# SCH_Easy-eda-E-xmas-board_2024-12-05.net
KiCad netlist of a schematic drawn in EasyEDA
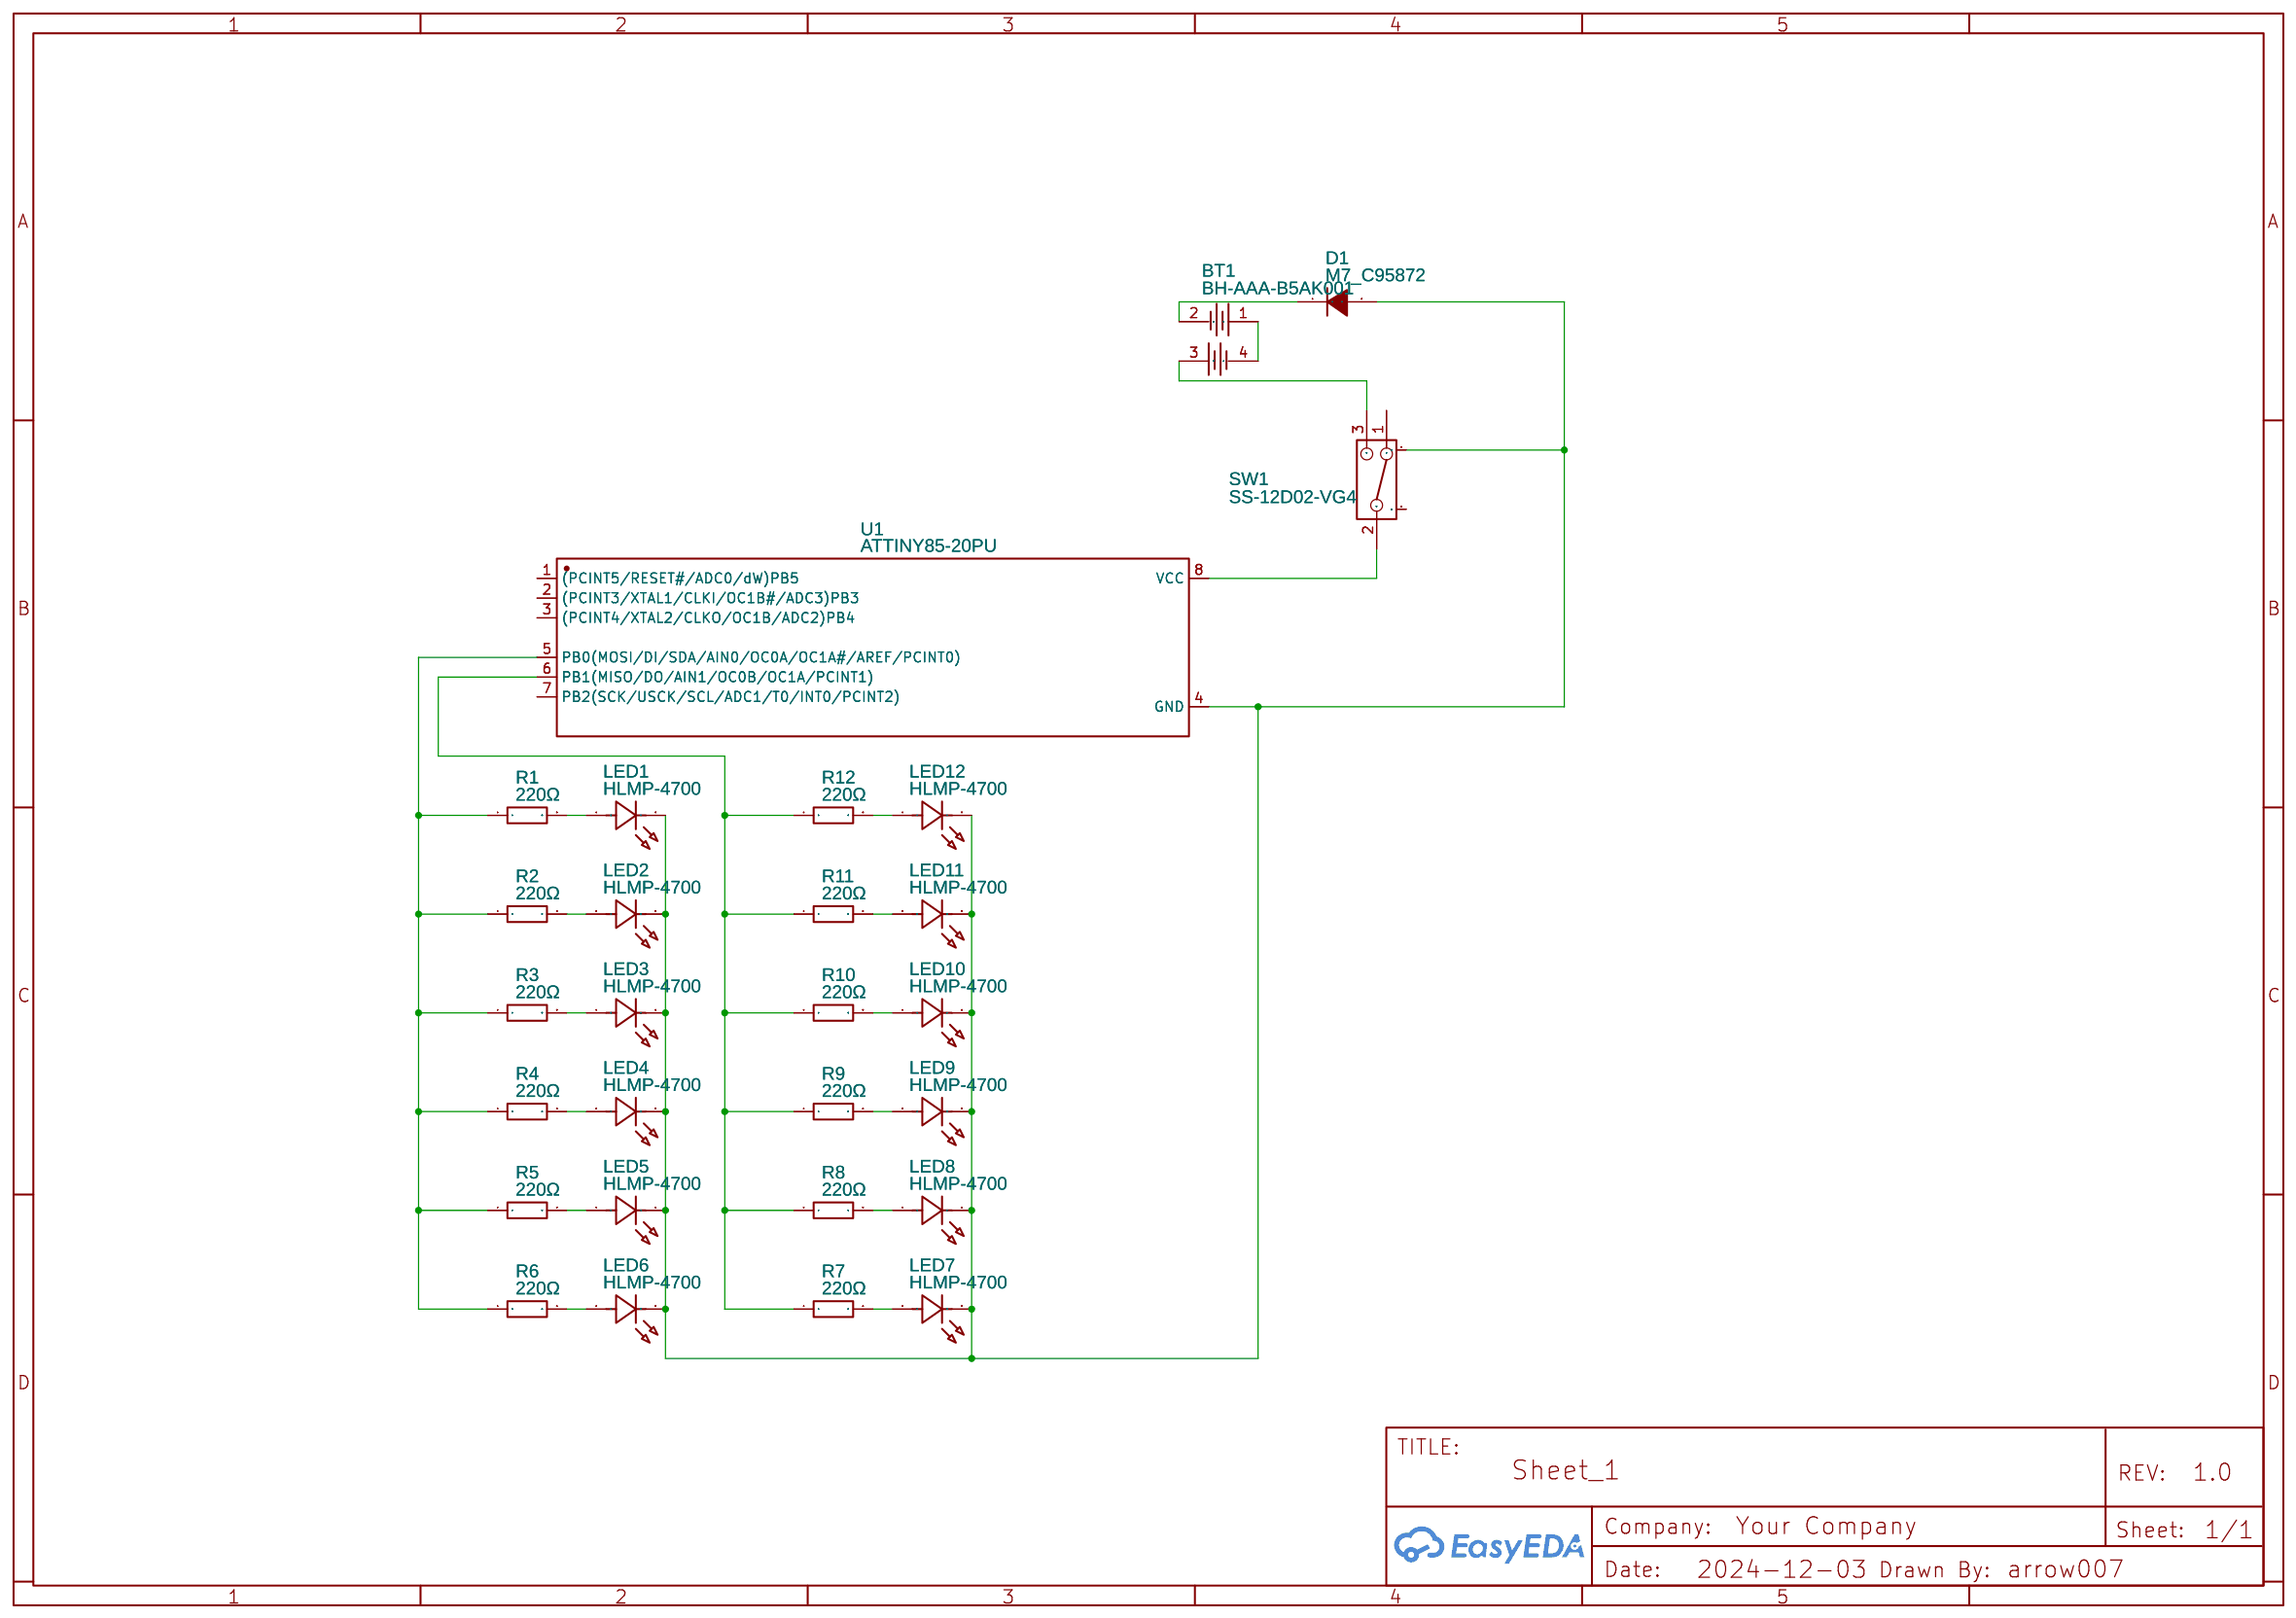
[diagram p0: schematic sheet]

(export (version "E")
  (design (tool "Eeschema 10.0.6"))
  (components
    (comp (ref "BT1")
      (value "BH-AAA-B5AK001")
      (fields (field (name "Manufacturer") "MYOUNG(美阳)"))
      (libsource (lib "") (part "BH-AAA-B5AK001"))
    )
    (comp (ref "D1")
      (value "M7_C95872")
      (fields (field (name "Manufacturer Part") "M7") (field (name "Manufacturer") "MDD(辰达半导体)"))
      (libsource (lib "") (part "M7_C95872"))
    )
    (comp (ref "LED1")
      (value "HLMP-4700")
      (fields (field (name "Manufacturer") "Broadcom/AVAGO(安华高)"))
      (libsource (lib "") (part "HLMP-4700"))
    )
    (comp (ref "LED2")
      (value "HLMP-4700")
      (fields (field (name "Manufacturer") "Broadcom/AVAGO(安华高)"))
      (libsource (lib "") (part "HLMP-4700"))
    )
    (comp (ref "LED3")
      (value "HLMP-4700")
      (fields (field (name "Manufacturer") "Broadcom/AVAGO(安华高)"))
      (libsource (lib "") (part "HLMP-4700"))
    )
    (comp (ref "LED4")
      (value "HLMP-4700")
      (fields (field (name "Manufacturer") "Broadcom/AVAGO(安华高)"))
      (libsource (lib "") (part "HLMP-4700"))
    )
    (comp (ref "LED5")
      (value "HLMP-4700")
      (fields (field (name "Manufacturer") "Broadcom/AVAGO(安华高)"))
      (libsource (lib "") (part "HLMP-4700"))
    )
    (comp (ref "LED6")
      (value "HLMP-4700")
      (fields (field (name "Manufacturer") "Broadcom/AVAGO(安华高)"))
      (libsource (lib "") (part "HLMP-4700"))
    )
    (comp (ref "LED7")
      (value "HLMP-4700")
      (fields (field (name "Manufacturer") "Broadcom/AVAGO(安华高)"))
      (libsource (lib "") (part "HLMP-4700"))
    )
    (comp (ref "LED8")
      (value "HLMP-4700")
      (fields (field (name "Manufacturer") "Broadcom/AVAGO(安华高)"))
      (libsource (lib "") (part "HLMP-4700"))
    )
    (comp (ref "LED9")
      (value "HLMP-4700")
      (fields (field (name "Manufacturer") "Broadcom/AVAGO(安华高)"))
      (libsource (lib "") (part "HLMP-4700"))
    )
    (comp (ref "LED10")
      (value "HLMP-4700")
      (fields (field (name "Manufacturer") "Broadcom/AVAGO(安华高)"))
      (libsource (lib "") (part "HLMP-4700"))
    )
    (comp (ref "LED11")
      (value "HLMP-4700")
      (fields (field (name "Manufacturer") "Broadcom/AVAGO(安华高)"))
      (libsource (lib "") (part "HLMP-4700"))
    )
    (comp (ref "LED12")
      (value "HLMP-4700")
      (fields (field (name "Manufacturer") "Broadcom/AVAGO(安华高)"))
      (libsource (lib "") (part "HLMP-4700"))
    )
    (comp (ref "R1")
      (value "220Ω")
      (fields (field (name "Manufacturer Part") "RM04JTN221") (field (name "Manufacturer") "大毅科技"))
      (libsource (lib "") (part "RM04JTN221"))
    )
    (comp (ref "R2")
      (value "220Ω")
      (fields (field (name "Manufacturer Part") "RM04JTN221") (field (name "Manufacturer") "大毅科技"))
      (libsource (lib "") (part "RM04JTN221"))
    )
    (comp (ref "R3")
      (value "220Ω")
      (fields (field (name "Manufacturer Part") "RM04JTN221") (field (name "Manufacturer") "大毅科技"))
      (libsource (lib "") (part "RM04JTN221"))
    )
    (comp (ref "R4")
      (value "220Ω")
      (fields (field (name "Manufacturer Part") "RM04JTN221") (field (name "Manufacturer") "大毅科技"))
      (libsource (lib "") (part "RM04JTN221"))
    )
    (comp (ref "R5")
      (value "220Ω")
      (fields (field (name "Manufacturer Part") "RM04JTN221") (field (name "Manufacturer") "大毅科技"))
      (libsource (lib "") (part "RM04JTN221"))
    )
    (comp (ref "R6")
      (value "220Ω")
      (fields (field (name "Manufacturer Part") "RM04JTN221") (field (name "Manufacturer") "大毅科技"))
      (libsource (lib "") (part "RM04JTN221"))
    )
    (comp (ref "R7")
      (value "220Ω")
      (fields (field (name "Manufacturer Part") "RM04JTN221") (field (name "Manufacturer") "大毅科技"))
      (libsource (lib "") (part "RM04JTN221"))
    )
    (comp (ref "R8")
      (value "220Ω")
      (fields (field (name "Manufacturer Part") "RM04JTN221") (field (name "Manufacturer") "大毅科技"))
      (libsource (lib "") (part "RM04JTN221"))
    )
    (comp (ref "R9")
      (value "220Ω")
      (fields (field (name "Manufacturer Part") "RM04JTN221") (field (name "Manufacturer") "大毅科技"))
      (libsource (lib "") (part "RM04JTN221"))
    )
    (comp (ref "R10")
      (value "220Ω")
      (fields (field (name "Manufacturer Part") "RM04JTN221") (field (name "Manufacturer") "大毅科技"))
      (libsource (lib "") (part "RM04JTN221"))
    )
    (comp (ref "R11")
      (value "220Ω")
      (fields (field (name "Manufacturer Part") "RM04JTN221") (field (name "Manufacturer") "大毅科技"))
      (libsource (lib "") (part "RM04JTN221"))
    )
    (comp (ref "R12")
      (value "220Ω")
      (fields (field (name "Manufacturer Part") "RM04JTN221") (field (name "Manufacturer") "大毅科技"))
      (libsource (lib "") (part "RM04JTN221"))
    )
    (comp (ref "SW1")
      (value "SS-12D02-VG4")
      (fields (field (name "Manufacturer") "韩国韩荣"))
      (libsource (lib "") (part "SS-12D02-VG4"))
    )
    (comp (ref "U1")
      (value "ATTINY85-20PU")
      (fields (field (name "Manufacturer") "MICROCHIP(美国微芯)"))
      (libsource (lib "") (part "ATTINY85-20PU"))
    )
  )
  (nets
    (net (code "1") (name "Net-(BT1-Pad1)") (class "Default")
      (node (ref "BT1") (pin "1") (pinfunction "1_1") (pintype "input"))
      (node (ref "BT1") (pin "4") (pinfunction "4_4") (pintype "input"))
    )
    (net (code "2") (name "Net-(BT1-Pad3)") (class "Default")
      (node (ref "BT1") (pin "3") (pinfunction "3_3") (pintype "input"))
      (node (ref "SW1") (pin "3") (pinfunction "3_3") (pintype "unspecified"))
    )
    (net (code "3") (name "Net-(D1-A)") (class "Default")
      (node (ref "D1") (pin "2") (pinfunction "A_2") (pintype "unspecified"))
      (node (ref "LED1") (pin "2") (pinfunction "K_2") (pintype "unspecified"))
      (node (ref "LED10") (pin "2") (pinfunction "K_2") (pintype "unspecified"))
      (node (ref "LED11") (pin "2") (pinfunction "K_2") (pintype "unspecified"))
      (node (ref "LED12") (pin "2") (pinfunction "K_2") (pintype "unspecified"))
      (node (ref "LED2") (pin "2") (pinfunction "K_2") (pintype "unspecified"))
      (node (ref "LED3") (pin "2") (pinfunction "K_2") (pintype "unspecified"))
      (node (ref "LED4") (pin "2") (pinfunction "K_2") (pintype "unspecified"))
      (node (ref "LED5") (pin "2") (pinfunction "K_2") (pintype "unspecified"))
      (node (ref "LED6") (pin "2") (pinfunction "K_2") (pintype "unspecified"))
      (node (ref "LED7") (pin "2") (pinfunction "K_2") (pintype "unspecified"))
      (node (ref "LED8") (pin "2") (pinfunction "K_2") (pintype "unspecified"))
      (node (ref "LED9") (pin "2") (pinfunction "K_2") (pintype "unspecified"))
      (node (ref "SW1") (pin "4") (pinfunction "4_4") (pintype "unspecified"))
      (node (ref "U1") (pin "4") (pinfunction "GND_4") (pintype "unspecified"))
    )
    (net (code "4") (name "Net-(D1-K)") (class "Default")
      (node (ref "BT1") (pin "2") (pinfunction "2_2") (pintype "input"))
      (node (ref "D1") (pin "1") (pinfunction "K_1") (pintype "unspecified"))
    )
    (net (code "5") (name "Net-(LED1-A)") (class "Default")
      (node (ref "LED1") (pin "1") (pinfunction "A_1") (pintype "unspecified"))
      (node (ref "R1") (pin "2") (pinfunction "2_2") (pintype "unspecified"))
    )
    (net (code "6") (name "Net-(LED2-A)") (class "Default")
      (node (ref "LED2") (pin "1") (pinfunction "A_1") (pintype "unspecified"))
      (node (ref "R2") (pin "2") (pinfunction "2_2") (pintype "unspecified"))
    )
    (net (code "7") (name "Net-(LED3-A)") (class "Default")
      (node (ref "LED3") (pin "1") (pinfunction "A_1") (pintype "unspecified"))
      (node (ref "R3") (pin "2") (pinfunction "2_2") (pintype "unspecified"))
    )
    (net (code "8") (name "Net-(LED4-A)") (class "Default")
      (node (ref "LED4") (pin "1") (pinfunction "A_1") (pintype "unspecified"))
      (node (ref "R4") (pin "2") (pinfunction "2_2") (pintype "unspecified"))
    )
    (net (code "9") (name "Net-(LED5-A)") (class "Default")
      (node (ref "LED5") (pin "1") (pinfunction "A_1") (pintype "unspecified"))
      (node (ref "R5") (pin "2") (pinfunction "2_2") (pintype "unspecified"))
    )
    (net (code "10") (name "Net-(LED6-A)") (class "Default")
      (node (ref "LED6") (pin "1") (pinfunction "A_1") (pintype "unspecified"))
      (node (ref "R6") (pin "2") (pinfunction "2_2") (pintype "unspecified"))
    )
    (net (code "11") (name "Net-(LED7-A)") (class "Default")
      (node (ref "LED7") (pin "1") (pinfunction "A_1") (pintype "unspecified"))
      (node (ref "R7") (pin "2") (pinfunction "2_2") (pintype "unspecified"))
    )
    (net (code "12") (name "Net-(LED8-A)") (class "Default")
      (node (ref "LED8") (pin "1") (pinfunction "A_1") (pintype "unspecified"))
      (node (ref "R8") (pin "2") (pinfunction "2_2") (pintype "unspecified"))
    )
    (net (code "13") (name "Net-(LED9-A)") (class "Default")
      (node (ref "LED9") (pin "1") (pinfunction "A_1") (pintype "unspecified"))
      (node (ref "R9") (pin "2") (pinfunction "2_2") (pintype "unspecified"))
    )
    (net (code "14") (name "Net-(LED10-A)") (class "Default")
      (node (ref "LED10") (pin "1") (pinfunction "A_1") (pintype "unspecified"))
      (node (ref "R10") (pin "2") (pinfunction "2_2") (pintype "unspecified"))
    )
    (net (code "15") (name "Net-(LED11-A)") (class "Default")
      (node (ref "LED11") (pin "1") (pinfunction "A_1") (pintype "unspecified"))
      (node (ref "R11") (pin "2") (pinfunction "2_2") (pintype "unspecified"))
    )
    (net (code "16") (name "Net-(LED12-A)") (class "Default")
      (node (ref "LED12") (pin "1") (pinfunction "A_1") (pintype "unspecified"))
      (node (ref "R12") (pin "2") (pinfunction "2_2") (pintype "unspecified"))
    )
    (net (code "17") (name "Net-(U1-PB0(MOSI{slash}DI{slash}SDA{slash}AIN0{slash}OC0A{slash}OC1A#{slash}AREF{slash}PCINT0))") (class "Default")
      (node (ref "R1") (pin "1") (pinfunction "1_1") (pintype "unspecified"))
      (node (ref "R2") (pin "1") (pinfunction "1_1") (pintype "unspecified"))
      (node (ref "R3") (pin "1") (pinfunction "1_1") (pintype "unspecified"))
      (node (ref "R4") (pin "1") (pinfunction "1_1") (pintype "unspecified"))
      (node (ref "R5") (pin "1") (pinfunction "1_1") (pintype "unspecified"))
      (node (ref "R6") (pin "1") (pinfunction "1_1") (pintype "unspecified"))
      (node (ref "U1") (pin "5") (pinfunction "PB0(MOSI/DI/SDA/AIN0/OC0A/OC1A#/AREF/PCINT0)_5") (pintype "unspecified"))
    )
    (net (code "18") (name "Net-(U1-PB1(MISO{slash}DO{slash}AIN1{slash}OC0B{slash}OC1A{slash}PCINT1))") (class "Default")
      (node (ref "R10") (pin "1") (pinfunction "1_1") (pintype "unspecified"))
      (node (ref "R11") (pin "1") (pinfunction "1_1") (pintype "unspecified"))
      (node (ref "R12") (pin "1") (pinfunction "1_1") (pintype "unspecified"))
      (node (ref "R7") (pin "1") (pinfunction "1_1") (pintype "unspecified"))
      (node (ref "R8") (pin "1") (pinfunction "1_1") (pintype "unspecified"))
      (node (ref "R9") (pin "1") (pinfunction "1_1") (pintype "unspecified"))
      (node (ref "U1") (pin "6") (pinfunction "PB1(MISO/DO/AIN1/OC0B/OC1A/PCINT1)_6") (pintype "unspecified"))
    )
    (net (code "19") (name "Net-(U1-VCC)") (class "Default")
      (node (ref "SW1") (pin "2") (pinfunction "2_2") (pintype "unspecified"))
      (node (ref "U1") (pin "8") (pinfunction "VCC_8") (pintype "unspecified"))
    )
    (net (code "20") (name "unconnected-(SW1-Pad1)") (class "Default")
      (node (ref "SW1") (pin "1") (pinfunction "1_1") (pintype "unspecified"))
    )
    (net (code "21") (name "unconnected-(SW1-Pad5)") (class "Default")
      (node (ref "SW1") (pin "5") (pinfunction "5_5") (pintype "unspecified"))
    )
    (net (code "22") (name "unconnected-(U1-(PCINT3{slash}XTAL1{slash}CLKI{slash}OC1B#{slash}ADC3)PB3-Pad2)") (class "Default")
      (node (ref "U1") (pin "2") (pinfunction "(PCINT3/XTAL1/CLKI/OC1B#/ADC3)PB3_2") (pintype "unspecified"))
    )
    (net (code "23") (name "unconnected-(U1-(PCINT4{slash}XTAL2{slash}CLKO{slash}OC1B{slash}ADC2)PB4-Pad3)") (class "Default")
      (node (ref "U1") (pin "3") (pinfunction "(PCINT4/XTAL2/CLKO/OC1B/ADC2)PB4_3") (pintype "unspecified"))
    )
    (net (code "24") (name "unconnected-(U1-(PCINT5{slash}RESET#{slash}ADC0{slash}dW)PB5-Pad1)") (class "Default")
      (node (ref "U1") (pin "1") (pinfunction "(PCINT5/RESET#/ADC0/dW)PB5_1") (pintype "unspecified"))
    )
    (net (code "25") (name "unconnected-(U1-PB2(SCK{slash}USCK{slash}SCL{slash}ADC1{slash}T0{slash}INT0{slash}PCINT2)-Pad7)") (class "Default")
      (node (ref "U1") (pin "7") (pinfunction "PB2(SCK/USCK/SCL/ADC1/T0/INT0/PCINT2)_7") (pintype "unspecified"))
    )
  )
)
